# H0AR6_Backend.net
KiCad netlist of a schematic drawn in Altium Designer
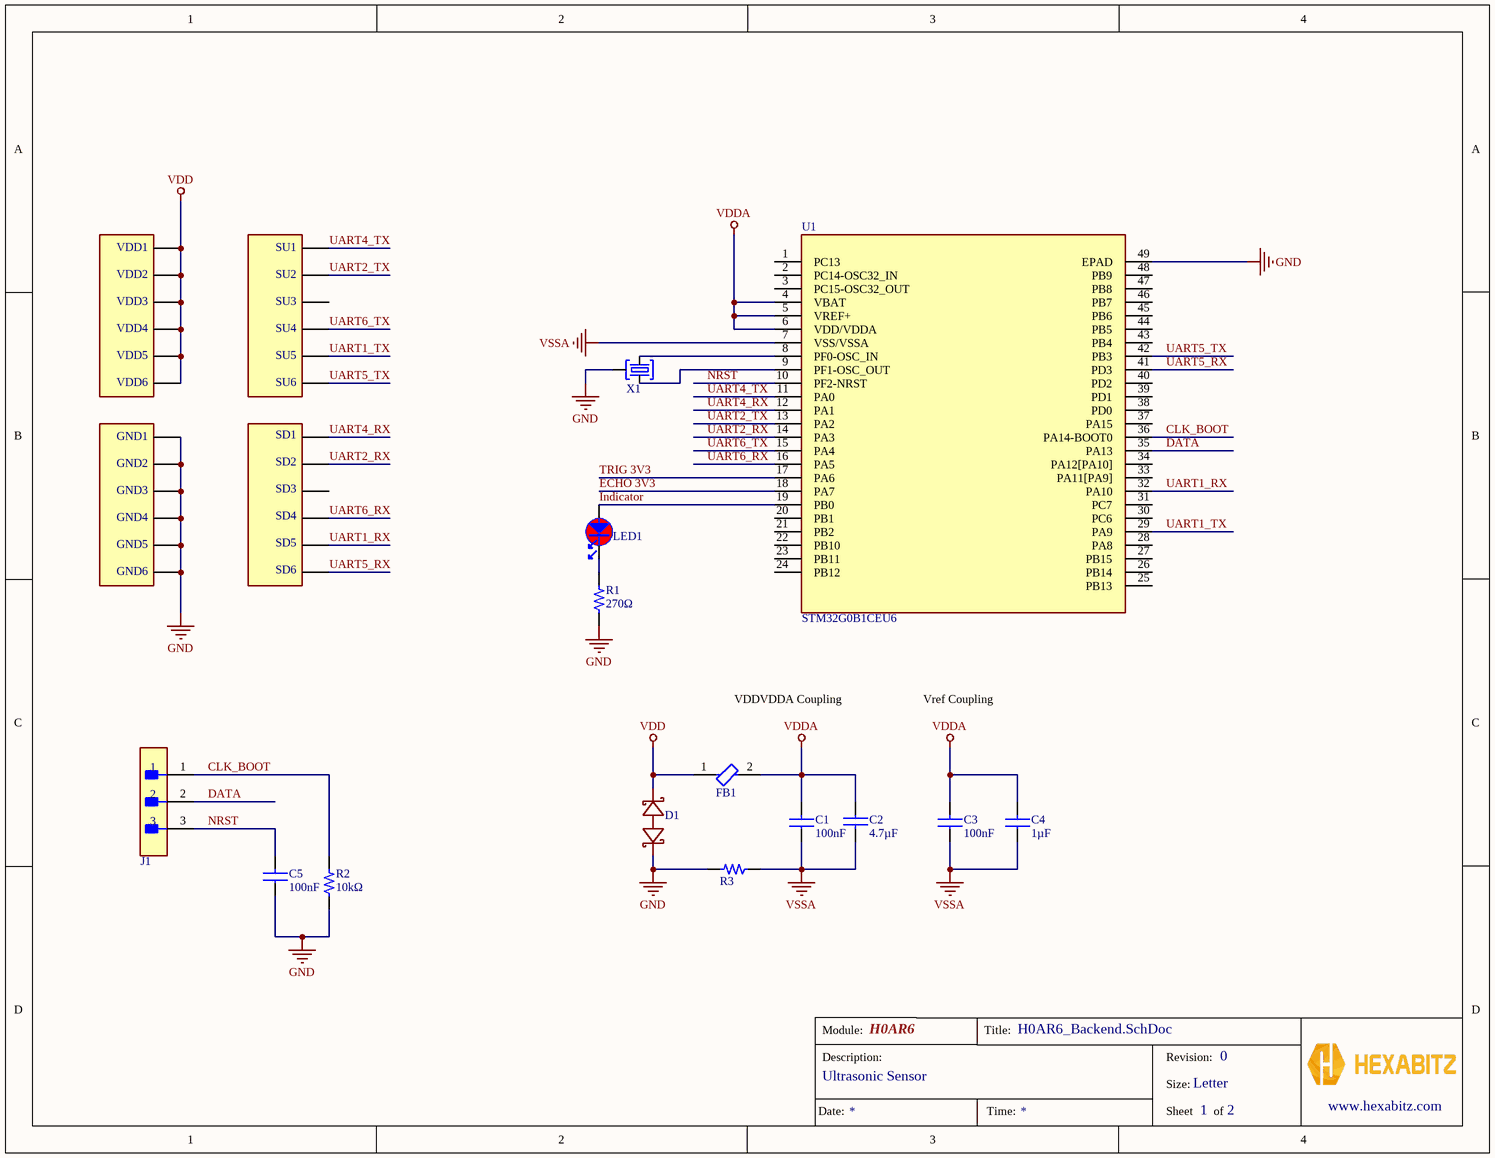
[diagram p0: H0AR6_Backend.SchDoc]

(export (version "E")
  (design (tool "Eeschema 10.0.6"))
  (components
    (comp (ref "C1")
      (value "100nF")
      (footprint "C0603")
      (fields
        (field (name "MANUFACTURER") "Samsung Electro-Mechanics")
        (field (name "MANUFACTURER PART NUMBER") "CL10B104KA8NNNC")
        (field (name "TOLERANCE") "10%")
      )
      (libsource (lib "Hexabitz Altium Library") (part "generic Capacitor"))
    )
    (comp (ref "C2")
      (value "4.7µF")
      (footprint "C0805")
      (fields
        (field (name "MANUFACTURER") "Samsung Electro-Mechanics")
        (field (name "MANUFACTURER PART NUMBER") "CL21X475KAQNNNE")
        (field (name "TOLERANCE") "10%")
      )
      (libsource (lib "Hexabitz Altium Library") (part "generic Capacitor"))
    )
    (comp (ref "C3")
      (value "100nF")
      (footprint "C0603")
      (fields
        (field (name "MANUFACTURER") "Samsung Electro-Mechanics")
        (field (name "MANUFACTURER PART NUMBER") "CL10B104KA8NNNC")
        (field (name "TOLERANCE") "10%")
      )
      (libsource (lib "Hexabitz Altium Library") (part "generic Capacitor"))
    )
    (comp (ref "C4")
      (value "1µF")
      (footprint "C0805")
      (description "Ceramic Capacitor, Ceramic, 16V, 10% +Tol, 10% -Tol, X7R, 15% TC, 1uF, Surface Mount, 0805")
      (fields
        (field (name "MANUFACTURER") "Yageo Group")
        (field (name "MANUFACTURER PART NUMBER") "CC0805KKX7R7BB105")
      )
      (libsource (lib "Hexabitz Altium Library") (part "generic Capacitor"))
    )
    (comp (ref "C5")
      (value "100nF")
      (footprint "C0603")
      (fields
        (field (name "MANUFACTURER") "Samsung Electro-Mechanics")
        (field (name "MANUFACTURER PART NUMBER") "CL10B104KA8NNNC")
        (field (name "TOLERANCE") "10%")
      )
      (libsource (lib "Hexabitz Altium Library") (part "generic Capacitor"))
    )
    (comp (ref "D1")
      (value "CDSOD323-T03SC")
      (footprint "SOD2513X114N")
      (description "A 3V, 350W, bi-directional, standard capacitance, SOD323 pkg TVS Diode ¦ Bourns CDSOD323-T03SC")
      (fields (field (name "MANUFACTURER") "Bourns"))
      (libsource (lib "Hexabitz Altium Library") (part "CDSOD323-T03SC"))
    )
    (comp (ref "FB1")
      (value "MMZ1608Y300B")
      (footprint "FP-MMZ1608-0_8-MFG")
      (description "Ferrite Beads 0603 30ohms 1500mA Signal Line AEC-Q200")
      (fields
        (field (name "MANUFACTURER") "TDK")
        (field (name "MANUFACTURER PART NUMBER") "MMZ1608Y300BTD25")
      )
      (libsource (lib "Hexabitz Altium Library") (part "MMZ1608Y300B"))
    )
    (comp (ref "GND1")
      (value "HEXABIT_UART_PORT")
      (footprint "HEXABIT_POWER_PORT_D")
      (libsource (lib "hexabitz_connectors.Library") (part "HEXABIT_POWER_PORT_D"))
    )
    (comp (ref "GND2")
      (value "HEXABIT_UART_PORT")
      (footprint "HEXABIT_POWER_PORT_D")
      (libsource (lib "hexabitz_connectors.Library") (part "HEXABIT_POWER_PORT_D"))
    )
    (comp (ref "GND3")
      (value "HEXABIT_UART_PORT")
      (footprint "HEXABIT_POWER_PORT_D")
      (libsource (lib "hexabitz_connectors.Library") (part "HEXABIT_POWER_PORT_D"))
    )
    (comp (ref "GND4")
      (value "HEXABIT_UART_PORT")
      (footprint "HEXABIT_POWER_PORT_D")
      (libsource (lib "hexabitz_connectors.Library") (part "HEXABIT_POWER_PORT_D"))
    )
    (comp (ref "GND5")
      (value "HEXABIT_UART_PORT")
      (footprint "HEXABIT_POWER_PORT_D")
      (libsource (lib "hexabitz_connectors.Library") (part "HEXABIT_POWER_PORT_D"))
    )
    (comp (ref "GND6")
      (value "HEXABIT_UART_PORT")
      (footprint "HEXABIT_POWER_PORT_D")
      (libsource (lib "hexabitz_connectors.Library") (part "HEXABIT_POWER_PORT_D"))
    )
    (comp (ref "J1")
      (value "TSW-103-14-G-S")
      (footprint "FP-TSW-103-14-G-S-MFG")
      (description "CONN HEADER VERT 3POS 2.54MM")
      (libsource (lib "Altium Content Vault") (part "cd3439d6ef35ae5d9b27ec4fdd3e828"))
    )
    (comp (ref "LED1")
      (value "VLMS1300-GS08")
      (footprint "FP-6_541-5092_01-4-MFG")
      (description "LED Uni-Color Super Red 639nm 2-Pin Chip 0603(1608Metric) T/R")
      (fields (field (name "MANUFACTURER") "Vishay Semiconductors"))
      (libsource (lib "Hexabitz Altium Library") (part "VLMS1300-GS08"))
    )
    (comp (ref "R1")
      (value "270Ω")
      (footprint "R0603")
      (description "Res Thick Film 0603 270 Ohm 5% 0.1W(1/10W) ±200ppm/C Pad SMD Automotive T/R")
      (fields
        (field (name "MANUFACTURER") "Panasonic")
        (field (name "MANUFACTURER PART NUMBER") "ERJ-3GEYJ271V")
      )
      (libsource (lib "Hexabitz Altium Library") (part "generic Resistor"))
    )
    (comp (ref "R2")
      (value "10kΩ")
      (footprint "R0603")
      (description "100mW Thick Film Resistors ±100ppm/℃ ±1% 10kΩ 0603 Chip Resistor - Surface Mount ROHS")
      (fields
        (field (name "MANUFACTURER") "Yageo Group")
        (field (name "MANUFACTURER PART NUMBER") "RC0603FR-0710KL")
      )
      (libsource (lib "") (part "generic Resistor_2"))
    )
    (comp (ref "R3")
      (value "Manufacturer Part Number")
      (footprint "R0603")
      (libsource (lib "") (part "generic Resistor_1"))
    )
    (comp (ref "SD1")
      (value "HEXABIT_UART_PORT")
      (footprint "HEXABIT_UART_PORT_D")
      (libsource (lib "hexabitz_connectors.Library") (part "HEXABIT_UART_PORT_D"))
    )
    (comp (ref "SD2")
      (value "HEXABIT_UART_PORT")
      (footprint "HEXABIT_UART_PORT_D")
      (libsource (lib "hexabitz_connectors.Library") (part "HEXABIT_UART_PORT_D"))
    )
    (comp (ref "SD3")
      (value "HEXABIT_UART_PORT")
      (footprint "HEXABIT_UART_PORT_D")
      (libsource (lib "hexabitz_connectors.Library") (part "HEXABIT_UART_PORT_D"))
    )
    (comp (ref "SD4")
      (value "HEXABIT_UART_PORT")
      (footprint "HEXABIT_UART_PORT_D")
      (libsource (lib "hexabitz_connectors.Library") (part "HEXABIT_UART_PORT_D"))
    )
    (comp (ref "SD5")
      (value "HEXABIT_UART_PORT")
      (footprint "HEXABIT_UART_PORT_D")
      (libsource (lib "hexabitz_connectors.Library") (part "HEXABIT_UART_PORT_D"))
    )
    (comp (ref "SD6")
      (value "HEXABIT_UART_PORT")
      (footprint "HEXABIT_UART_PORT_D")
      (libsource (lib "hexabitz_connectors.Library") (part "HEXABIT_UART_PORT_D"))
    )
    (comp (ref "SU1")
      (value "HEXABIT_UART_PORT")
      (footprint "HEXABIT_UART_PORT_U")
      (libsource (lib "hexabitz_connectors.Library") (part "HEXABIT_UART_PORT_U"))
    )
    (comp (ref "SU2")
      (value "HEXABIT_UART_PORT")
      (footprint "HEXABIT_UART_PORT_U")
      (libsource (lib "hexabitz_connectors.Library") (part "HEXABIT_UART_PORT_U"))
    )
    (comp (ref "SU3")
      (value "HEXABIT_UART_PORT")
      (footprint "HEXABIT_UART_PORT_U")
      (libsource (lib "hexabitz_connectors.Library") (part "HEXABIT_UART_PORT_U"))
    )
    (comp (ref "SU4")
      (value "HEXABIT_UART_PORT")
      (footprint "HEXABIT_UART_PORT_U")
      (libsource (lib "hexabitz_connectors.Library") (part "HEXABIT_UART_PORT_U"))
    )
    (comp (ref "SU5")
      (value "HEXABIT_UART_PORT")
      (footprint "HEXABIT_UART_PORT_U")
      (libsource (lib "hexabitz_connectors.Library") (part "HEXABIT_UART_PORT_U"))
    )
    (comp (ref "SU6")
      (value "HEXABIT_UART_PORT")
      (footprint "HEXABIT_UART_PORT_U")
      (libsource (lib "hexabitz_connectors.Library") (part "HEXABIT_UART_PORT_U"))
    )
    (comp (ref "U1")
      (value "STM32G0B1CEU6")
      (footprint "QFN50P700X700X65-49N-D")
      (description "MCU 32-bit ARM Cortex M0+ RISC 512KB Flash 1.8V/2.5V/3.3V 48-Pin UFQFPN EP Tray")
      (fields
        (field (name "MANUFACTURER") "STMicroelectronics")
        (field (name "MANUFACTURER PART NUMBER") "STM32G0B1CEU6")
      )
      (libsource (lib "Hexabitz Altium Library") (part "STM32G0B1CEU6"))
    )
    (comp (ref "VDD1")
      (value "HEXABIT_UART_PORT")
      (footprint "HEXABIT_POWER_PORT_U")
      (libsource (lib "hexabitz_connectors.Library") (part "HEXABIT_POWER_PORT_U"))
    )
    (comp (ref "VDD2")
      (value "HEXABIT_UART_PORT")
      (footprint "HEXABIT_POWER_PORT_U")
      (libsource (lib "hexabitz_connectors.Library") (part "HEXABIT_POWER_PORT_U"))
    )
    (comp (ref "VDD3")
      (value "HEXABIT_UART_PORT")
      (footprint "HEXABIT_POWER_PORT_U")
      (libsource (lib "hexabitz_connectors.Library") (part "HEXABIT_POWER_PORT_U"))
    )
    (comp (ref "VDD4")
      (value "HEXABIT_UART_PORT")
      (footprint "HEXABIT_POWER_PORT_U")
      (libsource (lib "hexabitz_connectors.Library") (part "HEXABIT_POWER_PORT_U"))
    )
    (comp (ref "VDD5")
      (value "HEXABIT_UART_PORT")
      (footprint "HEXABIT_POWER_PORT_U")
      (libsource (lib "hexabitz_connectors.Library") (part "HEXABIT_POWER_PORT_U"))
    )
    (comp (ref "VDD6")
      (value "HEXABIT_UART_PORT")
      (footprint "HEXABIT_POWER_PORT_U")
      (libsource (lib "hexabitz_connectors.Library") (part "HEXABIT_POWER_PORT_U"))
    )
    (comp (ref "X1")
      (value "CSTCE8M00G52Z-R0")
      (footprint "XTALL_CSTCE8M00G52")
      (description "Ceramic Resonator 8MHz ±0.5% (Tol) ±0.2% (Stability) 10pF 40Ohm 3-Pin CSMD T/R")
      (fields (field (name "MANUFACTURER") "Murata") (field (name "TOLERANCE") "0.5%"))
      (libsource (lib "Hexabitz Altium Library") (part "CSTCE8M00G52Z-R0"))
    )
  )
  (nets
    (net (code "1") (name "/CLK_BOOT") (class "Default")
      (node (ref "J1") (pin "1") (pinfunction "1_1") (pintype "passive"))
      (node (ref "R2") (pin "1") (pinfunction "1_1") (pintype "passive"))
      (node (ref "U1") (pin "36") (pinfunction "PA14-BOOT0_36") (pintype "passive"))
    )
    (net (code "2") (name "/DATA") (class "Default")
      (node (ref "J1") (pin "2") (pinfunction "2_2") (pintype "passive"))
      (node (ref "U1") (pin "35") (pinfunction "PA13_35") (pintype "passive"))
    )
    (net (code "3") (name "/ECHO 3V3") (class "Default")
      (node (ref "U1") (pin "18") (pinfunction "PA7_18") (pintype "passive"))
    )
    (net (code "4") (name "/Indicator") (class "Default")
      (node (ref "LED1") (pin "2") (pintype "passive"))
      (node (ref "U1") (pin "19") (pinfunction "PB0_19") (pintype "passive"))
    )
    (net (code "5") (name "/NRST") (class "Default")
      (node (ref "C5") (pin "2") (pinfunction "2_2") (pintype "passive"))
      (node (ref "J1") (pin "3") (pinfunction "3_3") (pintype "passive"))
      (node (ref "U1") (pin "10") (pinfunction "PF2-NRST_10") (pintype "passive"))
    )
    (net (code "6") (name "/TRIG 3V3") (class "Default")
      (node (ref "U1") (pin "17") (pinfunction "PA6_17") (pintype "passive"))
    )
    (net (code "7") (name "/UART1_RX") (class "Default")
      (node (ref "SD5") (pin "UART_D") (pinfunction "UART_D_UART_D") (pintype "passive"))
      (node (ref "U1") (pin "32") (pinfunction "PA10_32") (pintype "passive"))
    )
    (net (code "8") (name "/UART1_TX") (class "Default")
      (node (ref "SU5") (pin "UART_U") (pinfunction "UART_U_UART_U") (pintype "passive"))
      (node (ref "U1") (pin "29") (pinfunction "PA9_29") (pintype "passive"))
    )
    (net (code "9") (name "/UART2_RX") (class "Default")
      (node (ref "SD2") (pin "UART_D") (pinfunction "UART_D_UART_D") (pintype "passive"))
      (node (ref "U1") (pin "14") (pinfunction "PA3_14") (pintype "passive"))
    )
    (net (code "10") (name "/UART2_TX") (class "Default")
      (node (ref "SU2") (pin "UART_U") (pinfunction "UART_U_UART_U") (pintype "passive"))
      (node (ref "U1") (pin "13") (pinfunction "PA2_13") (pintype "passive"))
    )
    (net (code "11") (name "/UART4_RX") (class "Default")
      (node (ref "SD1") (pin "UART_D") (pinfunction "UART_D_UART_D") (pintype "passive"))
      (node (ref "U1") (pin "12") (pinfunction "PA1_12") (pintype "passive"))
    )
    (net (code "12") (name "/UART4_TX") (class "Default")
      (node (ref "SU1") (pin "UART_U") (pinfunction "UART_U_UART_U") (pintype "passive"))
      (node (ref "U1") (pin "11") (pinfunction "PA0_11") (pintype "passive"))
    )
    (net (code "13") (name "/UART5_RX") (class "Default")
      (node (ref "SD6") (pin "UART_D") (pinfunction "UART_D_UART_D") (pintype "passive"))
      (node (ref "U1") (pin "41") (pinfunction "PD3_41") (pintype "passive"))
    )
    (net (code "14") (name "/UART5_TX") (class "Default")
      (node (ref "SU6") (pin "UART_U") (pinfunction "UART_U_UART_U") (pintype "passive"))
      (node (ref "U1") (pin "42") (pinfunction "PB3_42") (pintype "passive"))
    )
    (net (code "15") (name "/UART6_RX") (class "Default")
      (node (ref "SD4") (pin "UART_D") (pinfunction "UART_D_UART_D") (pintype "passive"))
      (node (ref "U1") (pin "16") (pinfunction "PA5_16") (pintype "passive"))
    )
    (net (code "16") (name "/UART6_TX") (class "Default")
      (node (ref "SU4") (pin "UART_U") (pinfunction "UART_U_UART_U") (pintype "passive"))
      (node (ref "U1") (pin "15") (pinfunction "PA4_15") (pintype "passive"))
    )
    (net (code "17") (name "GND") (class "Default")
      (node (ref "C5") (pin "1") (pinfunction "1_1") (pintype "passive"))
      (node (ref "D1") (pin "1") (pinfunction "A_1") (pintype "passive"))
      (node (ref "GND1") (pin "Pwr_D") (pinfunction "Pwr_D_Pwr_D") (pintype "passive"))
      (node (ref "GND2") (pin "Pwr_D") (pinfunction "Pwr_D_Pwr_D") (pintype "passive"))
      (node (ref "GND3") (pin "Pwr_D") (pinfunction "Pwr_D_Pwr_D") (pintype "passive"))
      (node (ref "GND4") (pin "Pwr_D") (pinfunction "Pwr_D_Pwr_D") (pintype "passive"))
      (node (ref "GND5") (pin "Pwr_D") (pinfunction "Pwr_D_Pwr_D") (pintype "passive"))
      (node (ref "GND6") (pin "Pwr_D") (pinfunction "Pwr_D_Pwr_D") (pintype "passive"))
      (node (ref "R1") (pin "1") (pinfunction "1_1") (pintype "passive"))
      (node (ref "R2") (pin "2") (pinfunction "2_2") (pintype "passive"))
      (node (ref "R3") (pin "1") (pinfunction "1_1") (pintype "passive"))
      (node (ref "U1") (pin "49") (pinfunction "EPAD_49") (pintype "passive"))
      (node (ref "X1") (pin "P$2") (pinfunction "2_P$2") (pintype "passive"))
    )
    (net (code "18") (name "Net-(LED1-Pad1)") (class "Default")
      (node (ref "LED1") (pin "1") (pintype "passive"))
      (node (ref "R1") (pin "2") (pinfunction "2_2") (pintype "passive"))
    )
    (net (code "19") (name "Net-(U1-PF0-OSC_IN)") (class "Default")
      (node (ref "U1") (pin "8") (pinfunction "PF0-OSC_IN_8") (pintype "passive"))
      (node (ref "X1") (pin "P$3") (pinfunction "3_P$3") (pintype "passive"))
    )
    (net (code "20") (name "Net-(U1-PF1-OSC_OUT)") (class "Default")
      (node (ref "U1") (pin "9") (pinfunction "PF1-OSC_OUT_9") (pintype "passive"))
      (node (ref "X1") (pin "P$1") (pinfunction "1_P$1") (pintype "passive"))
    )
    (net (code "21") (name "VDD") (class "Default")
      (node (ref "D1") (pin "2") (pinfunction "C_2") (pintype "passive"))
      (node (ref "FB1") (pin "1") (pinfunction "1_1") (pintype "passive"))
      (node (ref "VDD1") (pin "Pwr_U") (pinfunction "Pwr_U_Pwr_U") (pintype "passive"))
      (node (ref "VDD2") (pin "Pwr_U") (pinfunction "Pwr_U_Pwr_U") (pintype "passive"))
      (node (ref "VDD3") (pin "Pwr_U") (pinfunction "Pwr_U_Pwr_U") (pintype "passive"))
      (node (ref "VDD4") (pin "Pwr_U") (pinfunction "Pwr_U_Pwr_U") (pintype "passive"))
      (node (ref "VDD5") (pin "Pwr_U") (pinfunction "Pwr_U_Pwr_U") (pintype "passive"))
      (node (ref "VDD6") (pin "Pwr_U") (pinfunction "Pwr_U_Pwr_U") (pintype "passive"))
    )
    (net (code "22") (name "VDDA") (class "Default")
      (node (ref "C1") (pin "2") (pinfunction "2_2") (pintype "passive"))
      (node (ref "C2") (pin "1") (pinfunction "1_1") (pintype "passive"))
      (node (ref "C3") (pin "2") (pinfunction "2_2") (pintype "passive"))
      (node (ref "C4") (pin "2") (pinfunction "2_2") (pintype "passive"))
      (node (ref "FB1") (pin "2") (pinfunction "2_2") (pintype "passive"))
      (node (ref "U1") (pin "4") (pinfunction "VBAT_4") (pintype "passive"))
      (node (ref "U1") (pin "5") (pinfunction "VREF+_5") (pintype "passive"))
      (node (ref "U1") (pin "6") (pinfunction "VDD/VDDA_6") (pintype "passive"))
    )
    (net (code "23") (name "VSSA") (class "Default")
      (node (ref "C1") (pin "1") (pinfunction "1_1") (pintype "passive"))
      (node (ref "C2") (pin "2") (pinfunction "2_2") (pintype "passive"))
      (node (ref "C3") (pin "1") (pinfunction "1_1") (pintype "passive"))
      (node (ref "C4") (pin "1") (pinfunction "1_1") (pintype "passive"))
      (node (ref "R3") (pin "2") (pinfunction "2_2") (pintype "passive"))
      (node (ref "U1") (pin "7") (pinfunction "VSS/VSSA_7") (pintype "passive"))
    )
    (net (code "24") (name "unconnected-(SD3-PadUART_D)") (class "Default")
      (node (ref "SD3") (pin "UART_D") (pinfunction "UART_D_UART_D") (pintype "passive"))
    )
    (net (code "25") (name "unconnected-(SU3-PadUART_U)") (class "Default")
      (node (ref "SU3") (pin "UART_U") (pinfunction "UART_U_UART_U") (pintype "passive"))
    )
    (net (code "26") (name "unconnected-(U1-PA8-Pad28)") (class "Default")
      (node (ref "U1") (pin "28") (pinfunction "PA8_28") (pintype "passive"))
    )
    (net (code "27") (name "unconnected-(U1-PA11[PA9]-Pad33)") (class "Default")
      (node (ref "U1") (pin "33") (pinfunction "PA11[PA9]_33") (pintype "passive"))
    )
    (net (code "28") (name "unconnected-(U1-PA12[PA10]-Pad34)") (class "Default")
      (node (ref "U1") (pin "34") (pinfunction "PA12[PA10]_34") (pintype "passive"))
    )
    (net (code "29") (name "unconnected-(U1-PA15-Pad37)") (class "Default")
      (node (ref "U1") (pin "37") (pinfunction "PA15_37") (pintype "passive"))
    )
    (net (code "30") (name "unconnected-(U1-PB1-Pad20)") (class "Default")
      (node (ref "U1") (pin "20") (pinfunction "PB1_20") (pintype "passive"))
    )
    (net (code "31") (name "unconnected-(U1-PB2-Pad21)") (class "Default")
      (node (ref "U1") (pin "21") (pinfunction "PB2_21") (pintype "passive"))
    )
    (net (code "32") (name "unconnected-(U1-PB4-Pad43)") (class "Default")
      (node (ref "U1") (pin "43") (pinfunction "PB4_43") (pintype "passive"))
    )
    (net (code "33") (name "unconnected-(U1-PB5-Pad44)") (class "Default")
      (node (ref "U1") (pin "44") (pinfunction "PB5_44") (pintype "passive"))
    )
    (net (code "34") (name "unconnected-(U1-PB6-Pad45)") (class "Default")
      (node (ref "U1") (pin "45") (pinfunction "PB6_45") (pintype "passive"))
    )
    (net (code "35") (name "unconnected-(U1-PB7-Pad46)") (class "Default")
      (node (ref "U1") (pin "46") (pinfunction "PB7_46") (pintype "passive"))
    )
    (net (code "36") (name "unconnected-(U1-PB8-Pad47)") (class "Default")
      (node (ref "U1") (pin "47") (pinfunction "PB8_47") (pintype "passive"))
    )
    (net (code "37") (name "unconnected-(U1-PB9-Pad48)") (class "Default")
      (node (ref "U1") (pin "48") (pinfunction "PB9_48") (pintype "passive"))
    )
    (net (code "38") (name "unconnected-(U1-PB10-Pad22)") (class "Default")
      (node (ref "U1") (pin "22") (pinfunction "PB10_22") (pintype "passive"))
    )
    (net (code "39") (name "unconnected-(U1-PB11-Pad23)") (class "Default")
      (node (ref "U1") (pin "23") (pinfunction "PB11_23") (pintype "passive"))
    )
    (net (code "40") (name "unconnected-(U1-PB12-Pad24)") (class "Default")
      (node (ref "U1") (pin "24") (pinfunction "PB12_24") (pintype "passive"))
    )
    (net (code "41") (name "unconnected-(U1-PB13-Pad25)") (class "Default")
      (node (ref "U1") (pin "25") (pinfunction "PB13_25") (pintype "passive"))
    )
    (net (code "42") (name "unconnected-(U1-PB14-Pad26)") (class "Default")
      (node (ref "U1") (pin "26") (pinfunction "PB14_26") (pintype "passive"))
    )
    (net (code "43") (name "unconnected-(U1-PB15-Pad27)") (class "Default")
      (node (ref "U1") (pin "27") (pinfunction "PB15_27") (pintype "passive"))
    )
    (net (code "44") (name "unconnected-(U1-PC6-Pad30)") (class "Default")
      (node (ref "U1") (pin "30") (pinfunction "PC6_30") (pintype "passive"))
    )
    (net (code "45") (name "unconnected-(U1-PC7-Pad31)") (class "Default")
      (node (ref "U1") (pin "31") (pinfunction "PC7_31") (pintype "passive"))
    )
    (net (code "46") (name "unconnected-(U1-PC13-Pad1)") (class "Default")
      (node (ref "U1") (pin "1") (pinfunction "PC13_1") (pintype "passive"))
    )
    (net (code "47") (name "unconnected-(U1-PC14-OSC32_IN-Pad2)") (class "Default")
      (node (ref "U1") (pin "2") (pinfunction "PC14-OSC32_IN_2") (pintype "passive"))
    )
    (net (code "48") (name "unconnected-(U1-PC15-OSC32_OUT-Pad3)") (class "Default")
      (node (ref "U1") (pin "3") (pinfunction "PC15-OSC32_OUT_3") (pintype "passive"))
    )
    (net (code "49") (name "unconnected-(U1-PD0-Pad38)") (class "Default")
      (node (ref "U1") (pin "38") (pinfunction "PD0_38") (pintype "passive"))
    )
    (net (code "50") (name "unconnected-(U1-PD1-Pad39)") (class "Default")
      (node (ref "U1") (pin "39") (pinfunction "PD1_39") (pintype "passive"))
    )
    (net (code "51") (name "unconnected-(U1-PD2-Pad40)") (class "Default")
      (node (ref "U1") (pin "40") (pinfunction "PD2_40") (pintype "passive"))
    )
  )
)
